# Frozen_Slimes_v2_MPU.net
KiCad netlist of a schematic drawn in EasyEDA
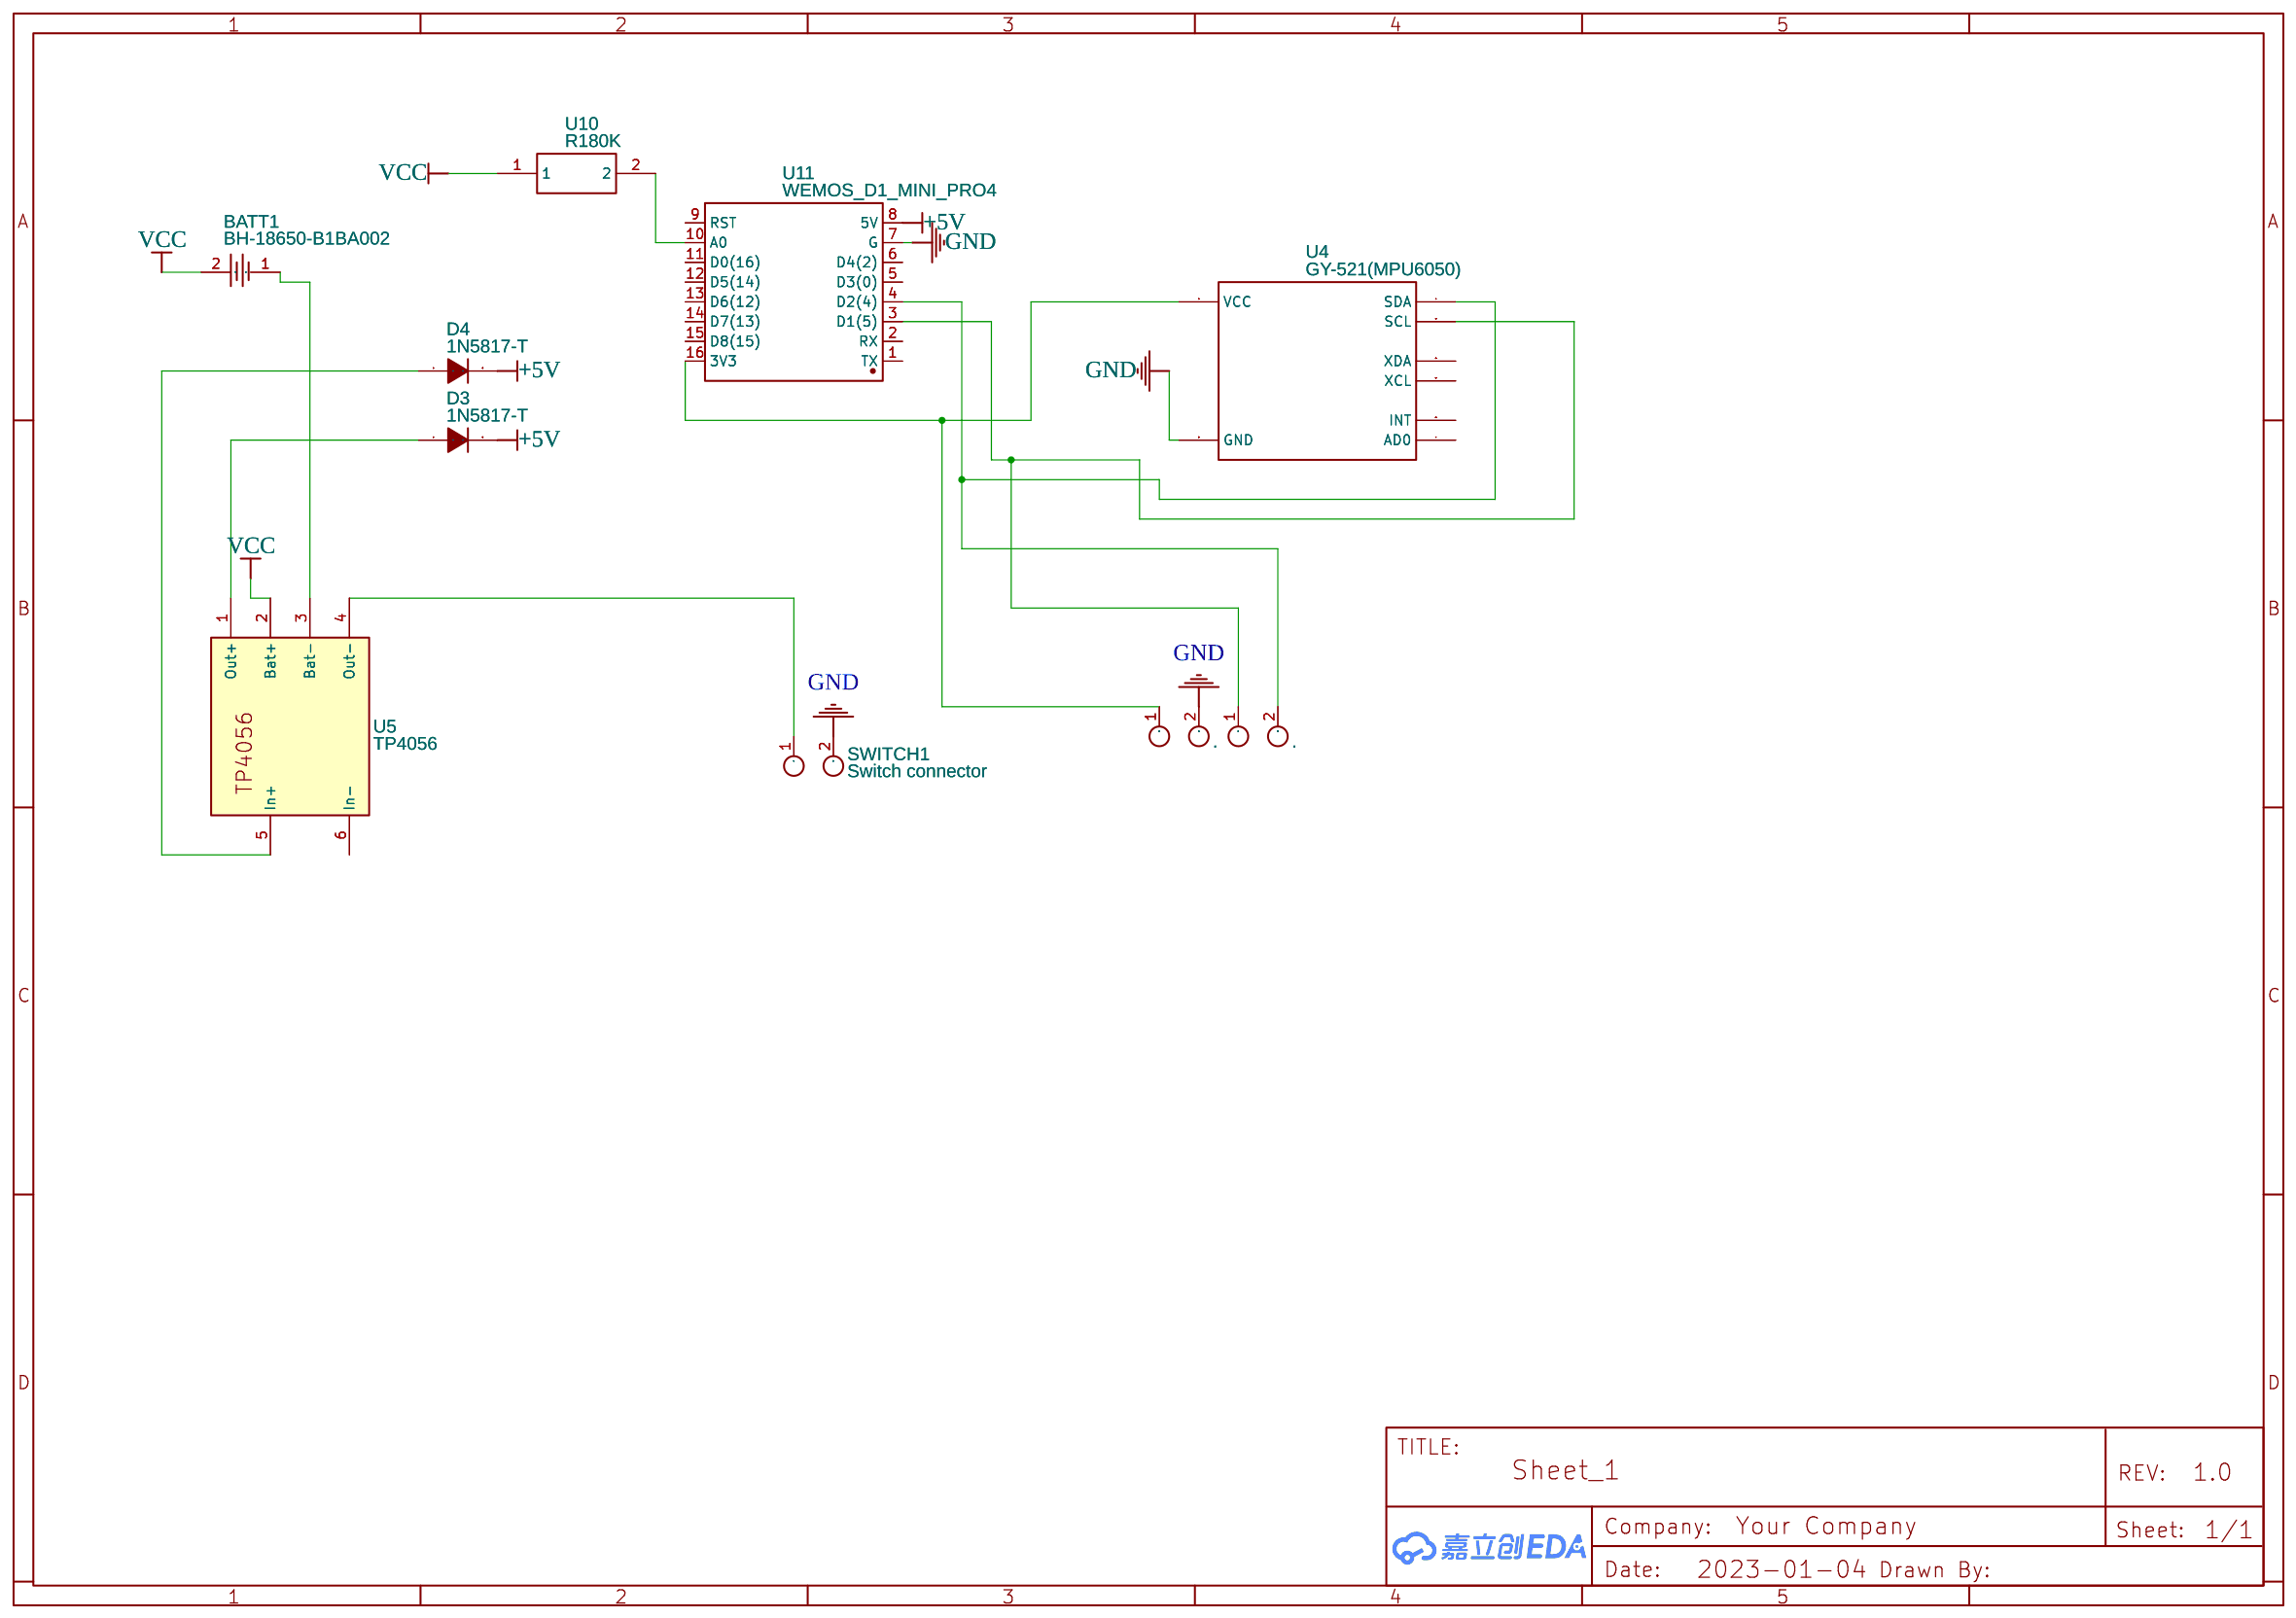
[diagram p0: schematic sheet]

(export (version "E")
  (design (tool "Eeschema 10.0.6"))
  (components
    (comp (ref "BATT1")
      (value "BH-18650-B1BA002")
      (fields (field (name "BOM_Supplier Part") "C2988620"))
      (libsource (lib "") (part "BH-18650-B1BA002"))
    )
    (comp (ref "D3")
      (value "1N5817-T")
      (fields (field (name "BOM_Supplier Part") "C507852"))
      (libsource (lib "") (part "1N5817-T"))
    )
    (comp (ref "D4")
      (value "1N5817-T")
      (fields (field (name "BOM_Supplier Part") "C507852"))
      (libsource (lib "") (part "1N5817-T"))
    )
    (comp (ref "SWITCH1") (value "Switch connector") (libsource (lib "") (part "2XSOLDER PAD_1")))
    (comp (ref "U4")
      (value "GY-521(MPU6050)")
      (fields (field (name "BOM_Manufacturer Part") "014802") (field (name "BOM_Supplier Part") "unknow"))
      (libsource (lib "") (part "GY-521(MPU6050)"))
    )
    (comp (ref "U5") (value "TP4056") (libsource (lib "") (part "TP4056")))
    (comp (ref "U8") (value ".") (libsource (lib "") (part "2XSOLDER PAD")))
    (comp (ref "U9") (value ".") (libsource (lib "") (part "2XSOLDER PAD")))
    (comp (ref "U10") (value "R180K") (libsource (lib "") (part "R180K")))
    (comp (ref "U11")
      (value "WEMOS_D1_MINI_PRO4")
      (fields
        (field (name "BOM_Manufacturer Part") "Wemos_D1_mini_Pro4")
        (field (name "BOM_Supplier Part") "C2837266")
      )
      (libsource (lib "") (part "WEMOS_D1_MINI_PRO4"))
    )
  )
  (nets
    (net (code "1") (name "+5V") (class "Default")
      (node (ref "D3") (pin "2") (pinfunction "K_2") (pintype "unspecified"))
      (node (ref "D4") (pin "2") (pinfunction "K_2") (pintype "unspecified"))
      (node (ref "U11") (pin "8") (pinfunction "5V_8") (pintype "unspecified"))
    )
    (net (code "2") (name "GND") (class "Default")
      (node (ref "SWITCH1") (pin "2") (pinfunction "2_2") (pintype "unspecified"))
      (node (ref "U11") (pin "7") (pinfunction "G_7") (pintype "unspecified"))
      (node (ref "U4") (pin "2") (pinfunction "GND_2") (pintype "unspecified"))
      (node (ref "U9") (pin "2") (pinfunction "2_2") (pintype "unspecified"))
    )
    (net (code "3") (name "Net-(D3-A)") (class "Default")
      (node (ref "D3") (pin "1") (pinfunction "A_1") (pintype "unspecified"))
      (node (ref "U5") (pin "1") (pinfunction "Out+_1") (pintype "unspecified"))
    )
    (net (code "4") (name "Net-(D4-A)") (class "Default")
      (node (ref "D4") (pin "1") (pinfunction "A_1") (pintype "unspecified"))
      (node (ref "U5") (pin "5") (pinfunction "In+_5") (pintype "unspecified"))
    )
    (net (code "5") (name "Net-(U5-Bat-)") (class "Default")
      (node (ref "BATT1") (pin "1") (pinfunction "1_1") (pintype "input"))
      (node (ref "U5") (pin "3") (pinfunction "Bat-_3") (pintype "unspecified"))
    )
    (net (code "6") (name "Net-(U5-Out-)") (class "Default")
      (node (ref "SWITCH1") (pin "1") (pinfunction "1_1") (pintype "unspecified"))
      (node (ref "U5") (pin "4") (pinfunction "Out-_4") (pintype "unspecified"))
    )
    (net (code "7") (name "Net-(U11-3V3)") (class "Default")
      (node (ref "U11") (pin "16") (pinfunction "3V3_16") (pintype "unspecified"))
      (node (ref "U4") (pin "1") (pinfunction "VCC_1") (pintype "unspecified"))
      (node (ref "U9") (pin "1") (pinfunction "1_1") (pintype "unspecified"))
    )
    (net (code "8") (name "Net-(U11-A0)") (class "Default")
      (node (ref "U10") (pin "2") (pinfunction "2_2") (pintype "unspecified"))
      (node (ref "U11") (pin "10") (pinfunction "A0_10") (pintype "unspecified"))
    )
    (net (code "9") (name "Net-(U11-D1(5))") (class "Default")
      (node (ref "U11") (pin "3") (pinfunction "D1(5)_3") (pintype "unspecified"))
      (node (ref "U4") (pin "3") (pinfunction "SCL_3") (pintype "unspecified"))
      (node (ref "U8") (pin "1") (pinfunction "1_1") (pintype "unspecified"))
    )
    (net (code "10") (name "Net-(U11-D2(4))") (class "Default")
      (node (ref "U11") (pin "4") (pinfunction "D2(4)_4") (pintype "unspecified"))
      (node (ref "U4") (pin "4") (pinfunction "SDA_4") (pintype "unspecified"))
      (node (ref "U8") (pin "2") (pinfunction "2_2") (pintype "unspecified"))
    )
    (net (code "11") (name "VCC") (class "Default")
      (node (ref "BATT1") (pin "2") (pinfunction "2_2") (pintype "input"))
      (node (ref "U10") (pin "1") (pinfunction "1_1") (pintype "unspecified"))
      (node (ref "U5") (pin "2") (pinfunction "Bat+_2") (pintype "unspecified"))
    )
    (net (code "12") (name "unconnected-(U4-AD0-Pad7)") (class "Default")
      (node (ref "U4") (pin "7") (pinfunction "AD0_7") (pintype "unspecified"))
    )
    (net (code "13") (name "unconnected-(U4-INT-Pad8)") (class "Default")
      (node (ref "U4") (pin "8") (pinfunction "INT_8") (pintype "unspecified"))
    )
    (net (code "14") (name "unconnected-(U4-XCL-Pad6)") (class "Default")
      (node (ref "U4") (pin "6") (pinfunction "XCL_6") (pintype "unspecified"))
    )
    (net (code "15") (name "unconnected-(U4-XDA-Pad5)") (class "Default")
      (node (ref "U4") (pin "5") (pinfunction "XDA_5") (pintype "unspecified"))
    )
    (net (code "16") (name "unconnected-(U5-In--Pad6)") (class "Default")
      (node (ref "U5") (pin "6") (pinfunction "In-_6") (pintype "unspecified"))
    )
    (net (code "17") (name "unconnected-(U11-D0(16)-Pad11)") (class "Default")
      (node (ref "U11") (pin "11") (pinfunction "D0(16)_11") (pintype "unspecified"))
    )
    (net (code "18") (name "unconnected-(U11-D3(0)-Pad5)") (class "Default")
      (node (ref "U11") (pin "5") (pinfunction "D3(0)_5") (pintype "unspecified"))
    )
    (net (code "19") (name "unconnected-(U11-D4(2)-Pad6)") (class "Default")
      (node (ref "U11") (pin "6") (pinfunction "D4(2)_6") (pintype "unspecified"))
    )
    (net (code "20") (name "unconnected-(U11-D5(14)-Pad12)") (class "Default")
      (node (ref "U11") (pin "12") (pinfunction "D5(14)_12") (pintype "unspecified"))
    )
    (net (code "21") (name "unconnected-(U11-D6(12)-Pad13)") (class "Default")
      (node (ref "U11") (pin "13") (pinfunction "D6(12)_13") (pintype "unspecified"))
    )
    (net (code "22") (name "unconnected-(U11-D7(13)-Pad14)") (class "Default")
      (node (ref "U11") (pin "14") (pinfunction "D7(13)_14") (pintype "unspecified"))
    )
    (net (code "23") (name "unconnected-(U11-D8(15)-Pad15)") (class "Default")
      (node (ref "U11") (pin "15") (pinfunction "D8(15)_15") (pintype "unspecified"))
    )
    (net (code "24") (name "unconnected-(U11-RST-Pad9)") (class "Default")
      (node (ref "U11") (pin "9") (pinfunction "RST_9") (pintype "unspecified"))
    )
    (net (code "25") (name "unconnected-(U11-RX-Pad2)") (class "Default")
      (node (ref "U11") (pin "2") (pinfunction "RX_2") (pintype "unspecified"))
    )
    (net (code "26") (name "unconnected-(U11-TX-Pad1)") (class "Default")
      (node (ref "U11") (pin "1") (pinfunction "TX_1") (pintype "unspecified"))
    )
  )
)
